# Sensor_Acquisition_Board_Rev2.net
KiCad netlist of a schematic drawn in EAGLE
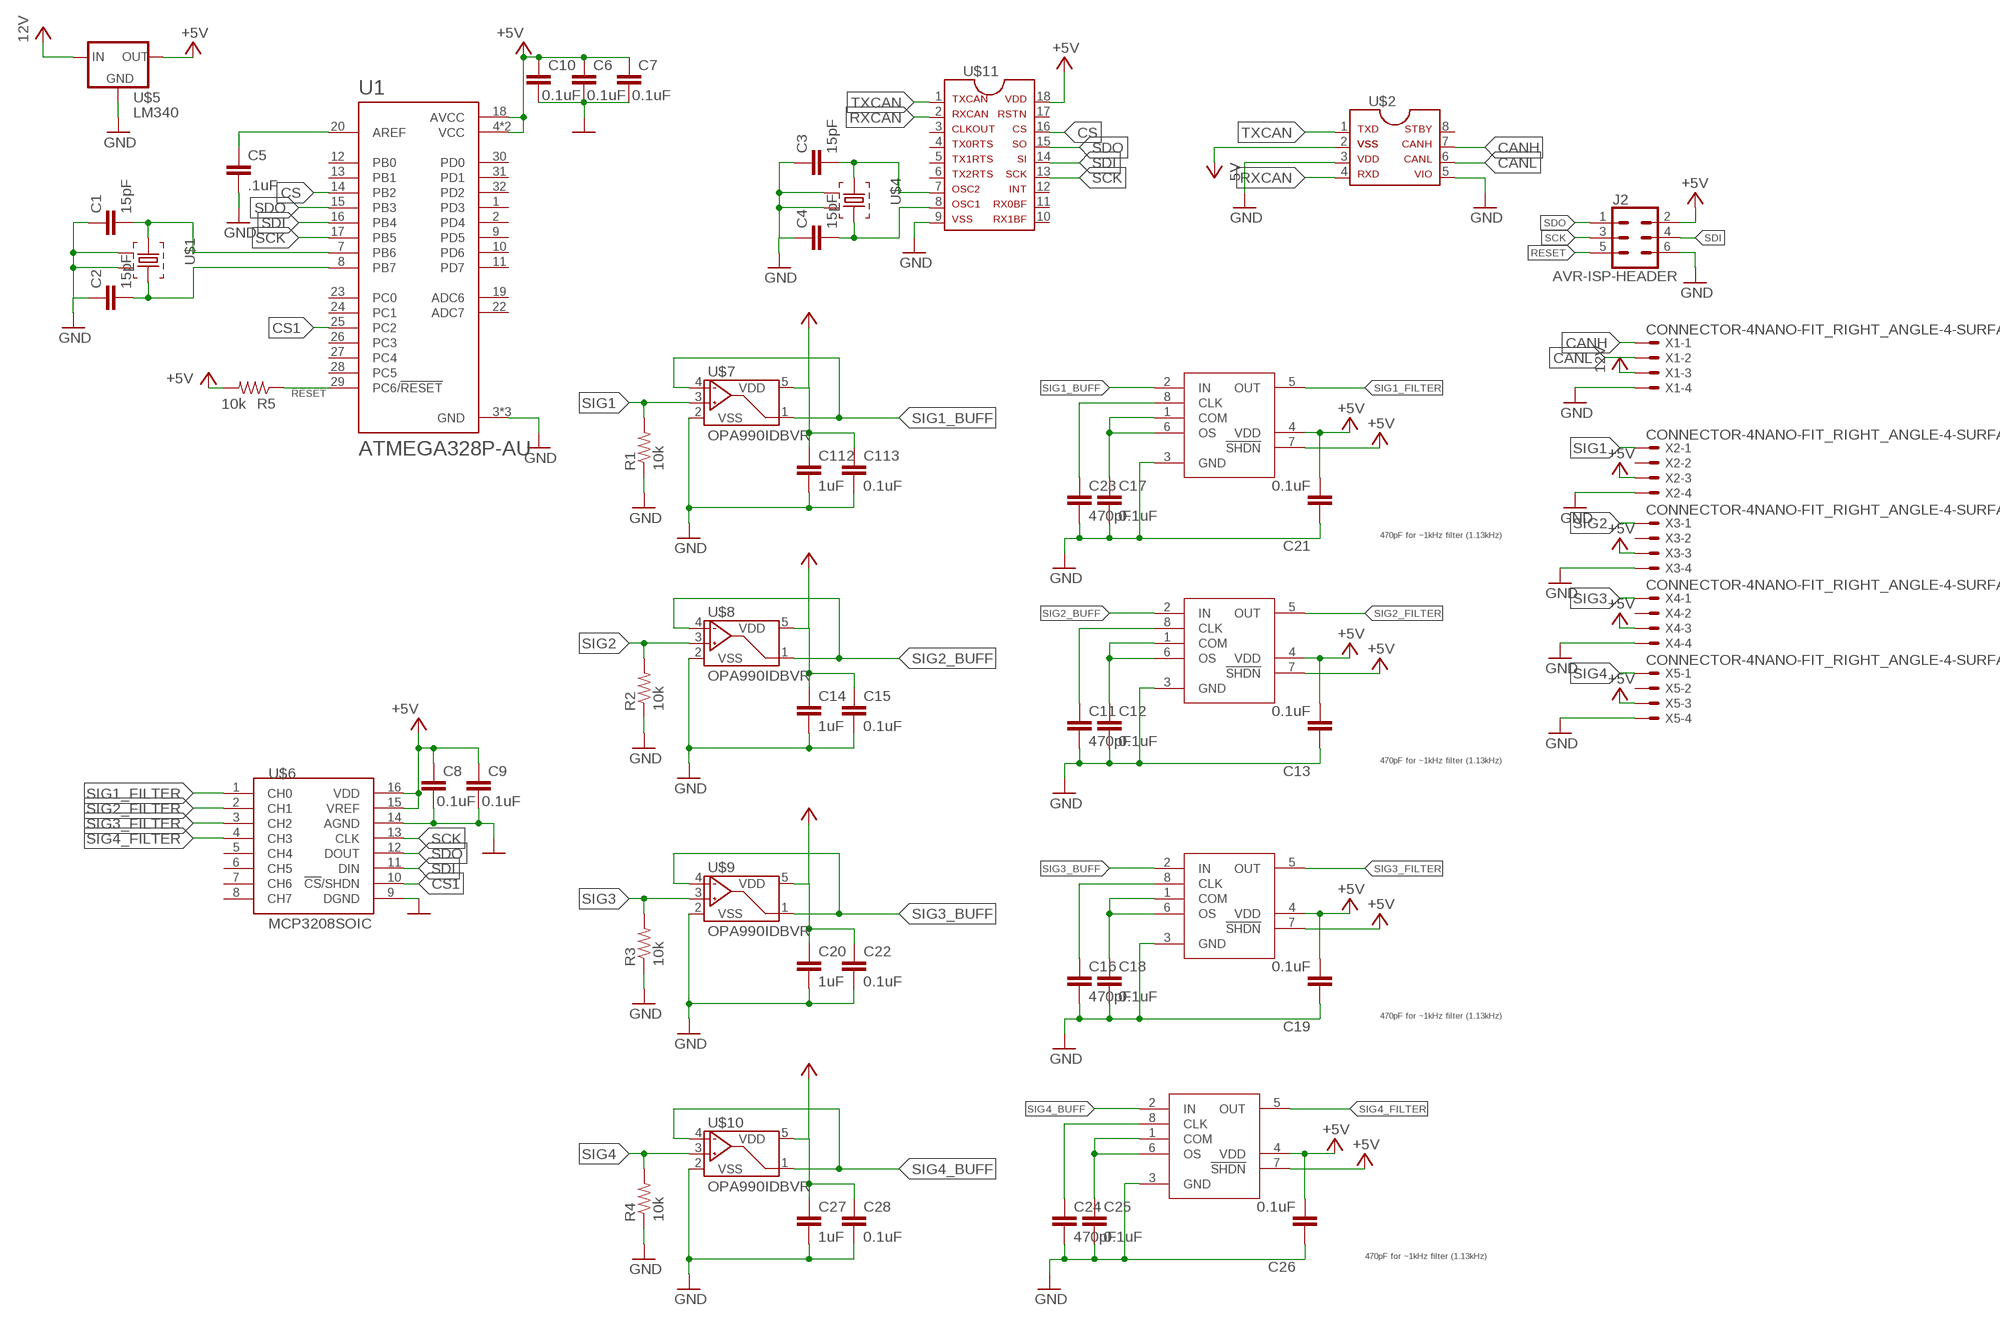
[diagram p0: schematic, sheet 1]

(export (version "E")
  (design (tool "Eeschema 10.0.6"))
  (components
    (comp (ref "C1")
      (value "15pF")
      (footprint "eagle-import:0603-CAP")
      (libsource (lib "eagle-import") (part "CAP0603-CAP"))
    )
    (comp (ref "C2")
      (value "15pF")
      (footprint "eagle-import:0603-CAP")
      (libsource (lib "eagle-import") (part "CAP0603-CAP"))
    )
    (comp (ref "C3")
      (value "15pF")
      (footprint "eagle-import:0603-CAP")
      (libsource (lib "eagle-import") (part "CAP0603-CAP"))
    )
    (comp (ref "C4")
      (value "15pF")
      (footprint "eagle-import:0603-CAP")
      (libsource (lib "eagle-import") (part "CAP0603-CAP"))
    )
    (comp (ref "C5")
      (value ".1uF")
      (footprint "eagle-import:0603-CAP")
      (libsource (lib "eagle-import") (part "CAP0603-CAP"))
    )
    (comp (ref "C6")
      (value "0.1uF")
      (footprint "eagle-import:0603-CAP")
      (libsource (lib "eagle-import") (part "CAP0603-CAP"))
    )
    (comp (ref "C7")
      (value "0.1uF")
      (footprint "eagle-import:0603-CAP")
      (libsource (lib "eagle-import") (part "CAP0603-CAP"))
    )
    (comp (ref "C8")
      (value "0.1uF")
      (footprint "eagle-import:0603-CAP")
      (libsource (lib "eagle-import") (part "CAP0603-CAP"))
    )
    (comp (ref "C9")
      (value "0.1uF")
      (footprint "eagle-import:0603-CAP")
      (libsource (lib "eagle-import") (part "CAP0603-CAP"))
    )
    (comp (ref "C10")
      (value "0.1uF")
      (footprint "eagle-import:0603-CAP")
      (libsource (lib "eagle-import") (part "CAP0603-CAP"))
    )
    (comp (ref "C11")
      (value "470pF")
      (footprint "eagle-import:0603-CAP")
      (libsource (lib "eagle-import") (part "CAP0603-CAP"))
    )
    (comp (ref "C12")
      (value "0.1uF")
      (footprint "eagle-import:0603-CAP")
      (libsource (lib "eagle-import") (part "CAP0603-CAP"))
    )
    (comp (ref "C13")
      (value "0.1uF")
      (footprint "eagle-import:0603-CAP")
      (libsource (lib "eagle-import") (part "CAP0603-CAP"))
    )
    (comp (ref "C14")
      (value "1uF")
      (footprint "eagle-import:0603-CAP")
      (libsource (lib "eagle-import") (part "CAP0603-CAP"))
    )
    (comp (ref "C15")
      (value "0.1uF")
      (footprint "eagle-import:0603-CAP")
      (libsource (lib "eagle-import") (part "CAP0603-CAP"))
    )
    (comp (ref "C16")
      (value "470pF")
      (footprint "eagle-import:0603-CAP")
      (libsource (lib "eagle-import") (part "CAP0603-CAP"))
    )
    (comp (ref "C17")
      (value "0.1uF")
      (footprint "eagle-import:0603-CAP")
      (libsource (lib "eagle-import") (part "CAP0603-CAP"))
    )
    (comp (ref "C18")
      (value "0.1uF")
      (footprint "eagle-import:0603-CAP")
      (libsource (lib "eagle-import") (part "CAP0603-CAP"))
    )
    (comp (ref "C19")
      (value "0.1uF")
      (footprint "eagle-import:0603-CAP")
      (libsource (lib "eagle-import") (part "CAP0603-CAP"))
    )
    (comp (ref "C20")
      (value "1uF")
      (footprint "eagle-import:0603-CAP")
      (libsource (lib "eagle-import") (part "CAP0603-CAP"))
    )
    (comp (ref "C21")
      (value "0.1uF")
      (footprint "eagle-import:0603-CAP")
      (libsource (lib "eagle-import") (part "CAP0603-CAP"))
    )
    (comp (ref "C22")
      (value "0.1uF")
      (footprint "eagle-import:0603-CAP")
      (libsource (lib "eagle-import") (part "CAP0603-CAP"))
    )
    (comp (ref "C23")
      (value "470pF")
      (footprint "eagle-import:0603-CAP")
      (libsource (lib "eagle-import") (part "CAP0603-CAP"))
    )
    (comp (ref "C24")
      (value "470pF")
      (footprint "eagle-import:0603-CAP")
      (libsource (lib "eagle-import") (part "CAP0603-CAP"))
    )
    (comp (ref "C25")
      (value "0.1uF")
      (footprint "eagle-import:0603-CAP")
      (libsource (lib "eagle-import") (part "CAP0603-CAP"))
    )
    (comp (ref "C26")
      (value "0.1uF")
      (footprint "eagle-import:0603-CAP")
      (libsource (lib "eagle-import") (part "CAP0603-CAP"))
    )
    (comp (ref "C27")
      (value "1uF")
      (footprint "eagle-import:0603-CAP")
      (libsource (lib "eagle-import") (part "CAP0603-CAP"))
    )
    (comp (ref "C28")
      (value "0.1uF")
      (footprint "eagle-import:0603-CAP")
      (libsource (lib "eagle-import") (part "CAP0603-CAP"))
    )
    (comp (ref "C112")
      (value "1uF")
      (footprint "eagle-import:0603-CAP")
      (libsource (lib "eagle-import") (part "CAP0603-CAP"))
    )
    (comp (ref "C113")
      (value "0.1uF")
      (footprint "eagle-import:0603-CAP")
      (libsource (lib "eagle-import") (part "CAP0603-CAP"))
    )
    (comp (ref "J2")
      (value "AVR-ISP-HEADER")
      (footprint "eagle-import:2X03@1")
      (libsource (lib "eagle-import") (part "AVR-ISP-HEADER"))
    )
    (comp (ref "R1")
      (value "10k")
      (footprint "eagle-import:0603-RES")
      (libsource (lib "eagle-import") (part "RESISTOR0603"))
    )
    (comp (ref "R2")
      (value "10k")
      (footprint "eagle-import:0603-RES")
      (libsource (lib "eagle-import") (part "RESISTOR0603"))
    )
    (comp (ref "R3")
      (value "10k")
      (footprint "eagle-import:0603-RES")
      (libsource (lib "eagle-import") (part "RESISTOR0603"))
    )
    (comp (ref "R4")
      (value "10k")
      (footprint "eagle-import:0603-RES")
      (libsource (lib "eagle-import") (part "RESISTOR0603"))
    )
    (comp (ref "R5")
      (value "10k")
      (footprint "eagle-import:0603-RES")
      (libsource (lib "eagle-import") (part "RESISTOR0603"))
    )
    (comp (ref "U$1")
      (value "ABM3B")
      (footprint "eagle-import:ABM3B")
      (libsource (lib "eagle-import") (part "ABM3B"))
    )
    (comp (ref "U$2")
      (value "MCP2562FDSOIC-08")
      (footprint "eagle-import:SOIC-08")
      (libsource (lib "eagle-import") (part "MCP2562FDSOIC-08"))
    )
    (comp (ref "U$4")
      (value "ABM3B")
      (footprint "eagle-import:ABM3B")
      (libsource (lib "eagle-import") (part "ABM3B"))
    )
    (comp (ref "U$5")
      (value "LM340")
      (footprint "eagle-import:SOT223")
      (libsource (lib "eagle-import") (part "LM340"))
    )
    (comp (ref "U$6")
      (value "MCP3208SOIC")
      (footprint "eagle-import:SOIC-16")
      (libsource (lib "eagle-import") (part "MCP3208SOIC"))
    )
    (comp (ref "U$7")
      (value "OPA990IDBVR")
      (footprint "eagle-import:SOT-23-5")
      (libsource (lib "eagle-import") (part "OPA990IDBVR"))
    )
    (comp (ref "U$8")
      (value "OPA990IDBVR")
      (footprint "eagle-import:SOT-23-5")
      (libsource (lib "eagle-import") (part "OPA990IDBVR"))
    )
    (comp (ref "U$9")
      (value "OPA990IDBVR")
      (footprint "eagle-import:SOT-23-5")
      (libsource (lib "eagle-import") (part "OPA990IDBVR"))
    )
    (comp (ref "U$10")
      (value "OPA990IDBVR")
      (footprint "eagle-import:SOT-23-5")
      (libsource (lib "eagle-import") (part "OPA990IDBVR"))
    )
    (comp (ref "U$11")
      (value "MCP2515SMD")
      (footprint "eagle-import:SOIC-18W")
      (libsource (lib "eagle-import") (part "MCP2515SMD"))
    )
    (comp (ref "U1")
      (value "ATMEGA328P-AU")
      (footprint "eagle-import:QFP80P900X900X120-32N")
      (fields (field (name "MF") "Microchip"))
      (libsource (lib "eagle-import") (part "ATMEGA328P-AU"))
    )
    (comp (ref "U2")
      (value "MAX7480")
      (footprint "eagle-import:SOP8")
      (libsource (lib "eagle-import") (part "MAX7400"))
    )
    (comp (ref "U3")
      (value "MAX7480")
      (footprint "eagle-import:SOP8")
      (libsource (lib "eagle-import") (part "MAX7400"))
    )
    (comp (ref "U4")
      (value "MAX7480")
      (footprint "eagle-import:SOP8")
      (libsource (lib "eagle-import") (part "MAX7400"))
    )
    (comp (ref "U24")
      (value "MAX7480")
      (footprint "eagle-import:SOP8")
      (libsource (lib "eagle-import") (part "MAX7400"))
    )
    (comp (ref "X1")
      (value "CONNECTOR-4NANO-FIT_RIGHT_ANGLE-4-SURFACE")
      (footprint "eagle-import:NANO-FIT_RIGHT_ANGLE-4-SURFACE")
      (libsource (lib "eagle-import") (part "CONNECTOR-4NANO-FIT_RIGHT_ANGLE-4-SURFACE"))
    )
    (comp (ref "X2")
      (value "CONNECTOR-4NANO-FIT_RIGHT_ANGLE-4-SURFACE")
      (footprint "eagle-import:NANO-FIT_RIGHT_ANGLE-4-SURFACE")
      (libsource (lib "eagle-import") (part "CONNECTOR-4NANO-FIT_RIGHT_ANGLE-4-SURFACE"))
    )
    (comp (ref "X3")
      (value "CONNECTOR-4NANO-FIT_RIGHT_ANGLE-4-SURFACE")
      (footprint "eagle-import:NANO-FIT_RIGHT_ANGLE-4-SURFACE")
      (libsource (lib "eagle-import") (part "CONNECTOR-4NANO-FIT_RIGHT_ANGLE-4-SURFACE"))
    )
    (comp (ref "X4")
      (value "CONNECTOR-4NANO-FIT_RIGHT_ANGLE-4-SURFACE")
      (footprint "eagle-import:NANO-FIT_RIGHT_ANGLE-4-SURFACE")
      (libsource (lib "eagle-import") (part "CONNECTOR-4NANO-FIT_RIGHT_ANGLE-4-SURFACE"))
    )
    (comp (ref "X5")
      (value "CONNECTOR-4NANO-FIT_RIGHT_ANGLE-4-SURFACE")
      (footprint "eagle-import:NANO-FIT_RIGHT_ANGLE-4-SURFACE")
      (libsource (lib "eagle-import") (part "CONNECTOR-4NANO-FIT_RIGHT_ANGLE-4-SURFACE"))
    )
  )
  (nets
    (net (code "1") (name "+5V") (class "Default")
      (node (ref "C10") (pin "1") (pinfunction "1_1") (pintype "passive"))
      (node (ref "C112") (pin "1") (pinfunction "1_1") (pintype "passive"))
      (node (ref "C113") (pin "1") (pinfunction "1_1") (pintype "passive"))
      (node (ref "C13") (pin "2") (pinfunction "2_2") (pintype "passive"))
      (node (ref "C14") (pin "1") (pinfunction "1_1") (pintype "passive"))
      (node (ref "C15") (pin "1") (pinfunction "1_1") (pintype "passive"))
      (node (ref "C19") (pin "2") (pinfunction "2_2") (pintype "passive"))
      (node (ref "C20") (pin "1") (pinfunction "1_1") (pintype "passive"))
      (node (ref "C21") (pin "2") (pinfunction "2_2") (pintype "passive"))
      (node (ref "C22") (pin "1") (pinfunction "1_1") (pintype "passive"))
      (node (ref "C26") (pin "2") (pinfunction "2_2") (pintype "passive"))
      (node (ref "C27") (pin "1") (pinfunction "1_1") (pintype "passive"))
      (node (ref "C28") (pin "1") (pinfunction "1_1") (pintype "passive"))
      (node (ref "C6") (pin "1") (pinfunction "1_1") (pintype "passive"))
      (node (ref "C7") (pin "1") (pinfunction "1_1") (pintype "passive"))
      (node (ref "C8") (pin "1") (pinfunction "1_1") (pintype "passive"))
      (node (ref "C9") (pin "1") (pinfunction "1_1") (pintype "passive"))
      (node (ref "J2") (pin "2") (pinfunction "2_2") (pintype "passive"))
      (node (ref "R5") (pin "2") (pinfunction "2_2") (pintype "passive"))
      (node (ref "U$10") (pin "5") (pinfunction "VDD_5") (pintype "passive"))
      (node (ref "U$11") (pin "18") (pinfunction "VDD_18") (pintype "passive"))
      (node (ref "U$5") (pin "3") (pinfunction "OUT_3") (pintype "output"))
      (node (ref "U$6") (pin "15") (pinfunction "VREF_15") (pintype "bidirectional"))
      (node (ref "U$6") (pin "16") (pinfunction "VDD_16") (pintype "bidirectional"))
      (node (ref "U$7") (pin "5") (pinfunction "VDD_5") (pintype "passive"))
      (node (ref "U$8") (pin "5") (pinfunction "VDD_5") (pintype "passive"))
      (node (ref "U$9") (pin "5") (pinfunction "VDD_5") (pintype "passive"))
      (node (ref "U1") (pin "18") (pinfunction "AVCC_18") (pintype "power_in"))
      (node (ref "U1") (pin "4") (pinfunction "VCC_4") (pintype "power_in"))
      (node (ref "U1") (pin "6") (pinfunction "VCC_6") (pintype "power_in"))
      (node (ref "U2") (pin "4") (pinfunction "VDD_4") (pintype "bidirectional"))
      (node (ref "U2") (pin "7") (pinfunction "~{SHDN}_7") (pintype "bidirectional"))
      (node (ref "U24") (pin "4") (pinfunction "VDD_4") (pintype "bidirectional"))
      (node (ref "U24") (pin "7") (pinfunction "~{SHDN}_7") (pintype "bidirectional"))
      (node (ref "U3") (pin "4") (pinfunction "VDD_4") (pintype "bidirectional"))
      (node (ref "U3") (pin "7") (pinfunction "~{SHDN}_7") (pintype "bidirectional"))
      (node (ref "U4") (pin "4") (pinfunction "VDD_4") (pintype "bidirectional"))
      (node (ref "U4") (pin "7") (pinfunction "~{SHDN}_7") (pintype "bidirectional"))
      (node (ref "X2") (pin "3") (pinfunction "S_3") (pintype "passive"))
      (node (ref "X3") (pin "3") (pinfunction "S_3") (pintype "passive"))
      (node (ref "X4") (pin "3") (pinfunction "S_3") (pintype "passive"))
      (node (ref "X5") (pin "3") (pinfunction "S_3") (pintype "passive"))
    )
    (net (code "2") (name "12V") (class "Default")
      (node (ref "U$2") (pin "2") (pinfunction "2_2") (pintype "passive"))
      (node (ref "U$5") (pin "1") (pinfunction "IN_1") (pintype "input"))
      (node (ref "X1") (pin "3") (pinfunction "S_3") (pintype "passive"))
    )
    (net (code "3") (name "CANH") (class "Default")
      (node (ref "U$2") (pin "7") (pinfunction "7_7") (pintype "passive"))
      (node (ref "X1") (pin "1") (pinfunction "S_1") (pintype "passive"))
    )
    (net (code "4") (name "CANL") (class "Default")
      (node (ref "U$2") (pin "6") (pinfunction "6_6") (pintype "passive"))
      (node (ref "X1") (pin "2") (pinfunction "S_2") (pintype "passive"))
    )
    (net (code "5") (name "CS") (class "Default")
      (node (ref "U$11") (pin "16") (pinfunction "CS_16") (pintype "passive"))
      (node (ref "U1") (pin "14") (pinfunction "PB2_14") (pintype "bidirectional"))
    )
    (net (code "6") (name "CS1") (class "Default")
      (node (ref "U$6") (pin "10") (pinfunction "~{CS}/SHDN_10") (pintype "bidirectional"))
      (node (ref "U1") (pin "25") (pinfunction "PC2_25") (pintype "bidirectional"))
    )
    (net (code "7") (name "GND") (class "Default")
      (node (ref "C1") (pin "1") (pinfunction "1_1") (pintype "passive"))
      (node (ref "C10") (pin "2") (pinfunction "2_2") (pintype "passive"))
      (node (ref "C11") (pin "2") (pinfunction "2_2") (pintype "passive"))
      (node (ref "C112") (pin "2") (pinfunction "2_2") (pintype "passive"))
      (node (ref "C113") (pin "2") (pinfunction "2_2") (pintype "passive"))
      (node (ref "C12") (pin "2") (pinfunction "2_2") (pintype "passive"))
      (node (ref "C13") (pin "1") (pinfunction "1_1") (pintype "passive"))
      (node (ref "C14") (pin "2") (pinfunction "2_2") (pintype "passive"))
      (node (ref "C15") (pin "2") (pinfunction "2_2") (pintype "passive"))
      (node (ref "C16") (pin "2") (pinfunction "2_2") (pintype "passive"))
      (node (ref "C17") (pin "2") (pinfunction "2_2") (pintype "passive"))
      (node (ref "C18") (pin "2") (pinfunction "2_2") (pintype "passive"))
      (node (ref "C19") (pin "1") (pinfunction "1_1") (pintype "passive"))
      (node (ref "C2") (pin "1") (pinfunction "1_1") (pintype "passive"))
      (node (ref "C20") (pin "2") (pinfunction "2_2") (pintype "passive"))
      (node (ref "C21") (pin "1") (pinfunction "1_1") (pintype "passive"))
      (node (ref "C22") (pin "2") (pinfunction "2_2") (pintype "passive"))
      (node (ref "C23") (pin "2") (pinfunction "2_2") (pintype "passive"))
      (node (ref "C24") (pin "2") (pinfunction "2_2") (pintype "passive"))
      (node (ref "C25") (pin "2") (pinfunction "2_2") (pintype "passive"))
      (node (ref "C26") (pin "1") (pinfunction "1_1") (pintype "passive"))
      (node (ref "C27") (pin "2") (pinfunction "2_2") (pintype "passive"))
      (node (ref "C28") (pin "2") (pinfunction "2_2") (pintype "passive"))
      (node (ref "C3") (pin "1") (pinfunction "1_1") (pintype "passive"))
      (node (ref "C4") (pin "1") (pinfunction "1_1") (pintype "passive"))
      (node (ref "C5") (pin "2") (pinfunction "2_2") (pintype "passive"))
      (node (ref "C6") (pin "2") (pinfunction "2_2") (pintype "passive"))
      (node (ref "C7") (pin "2") (pinfunction "2_2") (pintype "passive"))
      (node (ref "C8") (pin "2") (pinfunction "2_2") (pintype "passive"))
      (node (ref "C9") (pin "2") (pinfunction "2_2") (pintype "passive"))
      (node (ref "J2") (pin "6") (pinfunction "6_6") (pintype "passive"))
      (node (ref "R1") (pin "1") (pinfunction "1_1") (pintype "passive"))
      (node (ref "R2") (pin "1") (pinfunction "1_1") (pintype "passive"))
      (node (ref "R3") (pin "1") (pinfunction "1_1") (pintype "passive"))
      (node (ref "R4") (pin "1") (pinfunction "1_1") (pintype "passive"))
      (node (ref "U$1") (pin "GND") (pinfunction "GND_GND") (pintype "passive"))
      (node (ref "U$1") (pin "GND2") (pinfunction "GND2_GND2") (pintype "passive"))
      (node (ref "U$10") (pin "2") (pinfunction "VSS_2") (pintype "passive"))
      (node (ref "U$11") (pin "9") (pinfunction "VSS_9") (pintype "passive"))
      (node (ref "U$2") (pin "3") (pinfunction "3_3") (pintype "passive"))
      (node (ref "U$2") (pin "5") (pinfunction "5_5") (pintype "passive"))
      (node (ref "U$4") (pin "GND") (pinfunction "GND_GND") (pintype "passive"))
      (node (ref "U$4") (pin "GND2") (pinfunction "GND2_GND2") (pintype "passive"))
      (node (ref "U$5") (pin "2") (pinfunction "GND_2") (pintype "input"))
      (node (ref "U$5") (pin "4") (pinfunction "GND_4") (pintype "input"))
      (node (ref "U$6") (pin "14") (pinfunction "AGND_14") (pintype "bidirectional"))
      (node (ref "U$6") (pin "9") (pinfunction "DGND_9") (pintype "bidirectional"))
      (node (ref "U$7") (pin "2") (pinfunction "VSS_2") (pintype "passive"))
      (node (ref "U$8") (pin "2") (pinfunction "VSS_2") (pintype "passive"))
      (node (ref "U$9") (pin "2") (pinfunction "VSS_2") (pintype "passive"))
      (node (ref "U1") (pin "21") (pinfunction "GND_21") (pintype "power_in"))
      (node (ref "U1") (pin "3") (pinfunction "GND_3") (pintype "power_in"))
      (node (ref "U1") (pin "5") (pinfunction "GND_5") (pintype "power_in"))
      (node (ref "U2") (pin "3") (pinfunction "GND_3") (pintype "bidirectional"))
      (node (ref "U24") (pin "3") (pinfunction "GND_3") (pintype "bidirectional"))
      (node (ref "U3") (pin "3") (pinfunction "GND_3") (pintype "bidirectional"))
      (node (ref "U4") (pin "3") (pinfunction "GND_3") (pintype "bidirectional"))
      (node (ref "X1") (pin "4") (pinfunction "S_4") (pintype "passive"))
      (node (ref "X2") (pin "4") (pinfunction "S_4") (pintype "passive"))
      (node (ref "X3") (pin "4") (pinfunction "S_4") (pintype "passive"))
      (node (ref "X4") (pin "4") (pinfunction "S_4") (pintype "passive"))
      (node (ref "X5") (pin "4") (pinfunction "S_4") (pintype "passive"))
    )
    (net (code "8") (name "Net-(U$11-OSC1)") (class "Default")
      (node (ref "C4") (pin "2") (pinfunction "2_2") (pintype "passive"))
      (node (ref "U$11") (pin "8") (pinfunction "OSC1_8") (pintype "passive"))
      (node (ref "U$4") (pin "3") (pinfunction "3_3") (pintype "passive"))
    )
    (net (code "9") (name "Net-(U$11-OSC2)") (class "Default")
      (node (ref "C3") (pin "2") (pinfunction "2_2") (pintype "passive"))
      (node (ref "U$11") (pin "7") (pinfunction "OSC2_7") (pintype "passive"))
      (node (ref "U$4") (pin "1") (pinfunction "1_1") (pintype "passive"))
    )
    (net (code "10") (name "Net-(U1-AREF)") (class "Default")
      (node (ref "C5") (pin "1") (pinfunction "1_1") (pintype "passive"))
      (node (ref "U1") (pin "20") (pinfunction "AREF_20") (pintype "input"))
    )
    (net (code "11") (name "Net-(U1-PB6)") (class "Default")
      (node (ref "C1") (pin "2") (pinfunction "2_2") (pintype "passive"))
      (node (ref "U$1") (pin "1") (pinfunction "1_1") (pintype "passive"))
      (node (ref "U1") (pin "7") (pinfunction "PB6_7") (pintype "bidirectional"))
    )
    (net (code "12") (name "Net-(U1-PB7)") (class "Default")
      (node (ref "C2") (pin "2") (pinfunction "2_2") (pintype "passive"))
      (node (ref "U$1") (pin "3") (pinfunction "3_3") (pintype "passive"))
      (node (ref "U1") (pin "8") (pinfunction "PB7_8") (pintype "bidirectional"))
    )
    (net (code "13") (name "Net-(U2-CLK)") (class "Default")
      (node (ref "C11") (pin "1") (pinfunction "1_1") (pintype "passive"))
      (node (ref "U2") (pin "8") (pinfunction "CLK_8") (pintype "bidirectional"))
    )
    (net (code "14") (name "Net-(U2-COM)") (class "Default")
      (node (ref "C12") (pin "1") (pinfunction "1_1") (pintype "passive"))
      (node (ref "U2") (pin "1") (pinfunction "COM_1") (pintype "bidirectional"))
      (node (ref "U2") (pin "6") (pinfunction "OS_6") (pintype "bidirectional"))
    )
    (net (code "15") (name "Net-(U3-CLK)") (class "Default")
      (node (ref "C16") (pin "1") (pinfunction "1_1") (pintype "passive"))
      (node (ref "U3") (pin "8") (pinfunction "CLK_8") (pintype "bidirectional"))
    )
    (net (code "16") (name "Net-(U3-COM)") (class "Default")
      (node (ref "C18") (pin "1") (pinfunction "1_1") (pintype "passive"))
      (node (ref "U3") (pin "1") (pinfunction "COM_1") (pintype "bidirectional"))
      (node (ref "U3") (pin "6") (pinfunction "OS_6") (pintype "bidirectional"))
    )
    (net (code "17") (name "Net-(U4-CLK)") (class "Default")
      (node (ref "C24") (pin "1") (pinfunction "1_1") (pintype "passive"))
      (node (ref "U4") (pin "8") (pinfunction "CLK_8") (pintype "bidirectional"))
    )
    (net (code "18") (name "Net-(U4-COM)") (class "Default")
      (node (ref "C25") (pin "1") (pinfunction "1_1") (pintype "passive"))
      (node (ref "U4") (pin "1") (pinfunction "COM_1") (pintype "bidirectional"))
      (node (ref "U4") (pin "6") (pinfunction "OS_6") (pintype "bidirectional"))
    )
    (net (code "19") (name "Net-(U24-CLK)") (class "Default")
      (node (ref "C23") (pin "1") (pinfunction "1_1") (pintype "passive"))
      (node (ref "U24") (pin "8") (pinfunction "CLK_8") (pintype "bidirectional"))
    )
    (net (code "20") (name "Net-(U24-COM)") (class "Default")
      (node (ref "C17") (pin "1") (pinfunction "1_1") (pintype "passive"))
      (node (ref "U24") (pin "1") (pinfunction "COM_1") (pintype "bidirectional"))
      (node (ref "U24") (pin "6") (pinfunction "OS_6") (pintype "bidirectional"))
    )
    (net (code "21") (name "RESET") (class "Default")
      (node (ref "J2") (pin "5") (pinfunction "5_5") (pintype "passive"))
      (node (ref "R5") (pin "1") (pinfunction "1_1") (pintype "passive"))
      (node (ref "U1") (pin "29") (pinfunction "PC6/~{RESET}_29") (pintype "bidirectional"))
    )
    (net (code "22") (name "RXCAN") (class "Default")
      (node (ref "U$11") (pin "2") (pinfunction "RXCAN_2") (pintype "passive"))
      (node (ref "U$2") (pin "4") (pinfunction "4_4") (pintype "passive"))
    )
    (net (code "23") (name "SCK") (class "Default")
      (node (ref "J2") (pin "3") (pinfunction "3_3") (pintype "passive"))
      (node (ref "U$11") (pin "13") (pinfunction "SCK_13") (pintype "passive"))
      (node (ref "U$6") (pin "13") (pinfunction "CLK_13") (pintype "bidirectional"))
      (node (ref "U1") (pin "17") (pinfunction "PB5_17") (pintype "bidirectional"))
    )
    (net (code "24") (name "SDI") (class "Default")
      (node (ref "J2") (pin "4") (pinfunction "4_4") (pintype "passive"))
      (node (ref "U$11") (pin "14") (pinfunction "SI_14") (pintype "passive"))
      (node (ref "U$6") (pin "11") (pinfunction "DIN_11") (pintype "bidirectional"))
      (node (ref "U1") (pin "16") (pinfunction "PB4_16") (pintype "bidirectional"))
    )
    (net (code "25") (name "SDO") (class "Default")
      (node (ref "J2") (pin "1") (pinfunction "1_1") (pintype "passive"))
      (node (ref "U$11") (pin "15") (pinfunction "SO_15") (pintype "passive"))
      (node (ref "U$6") (pin "12") (pinfunction "DOUT_12") (pintype "bidirectional"))
      (node (ref "U1") (pin "15") (pinfunction "PB3_15") (pintype "bidirectional"))
    )
    (net (code "26") (name "SIG1") (class "Default")
      (node (ref "R1") (pin "2") (pinfunction "2_2") (pintype "passive"))
      (node (ref "U$7") (pin "3") (pinfunction "VIN+_3") (pintype "passive"))
      (node (ref "X2") (pin "1") (pinfunction "S_1") (pintype "passive"))
    )
    (net (code "27") (name "SIG1_BUFF") (class "Default")
      (node (ref "U$7") (pin "1") (pinfunction "VOUT_1") (pintype "passive"))
      (node (ref "U$7") (pin "4") (pinfunction "VIN-_4") (pintype "passive"))
      (node (ref "U24") (pin "2") (pinfunction "IN_2") (pintype "bidirectional"))
    )
    (net (code "28") (name "SIG1_FILTER") (class "Default")
      (node (ref "U$6") (pin "1") (pinfunction "CH0_1") (pintype "bidirectional"))
      (node (ref "U24") (pin "5") (pinfunction "OUT_5") (pintype "bidirectional"))
    )
    (net (code "29") (name "SIG2") (class "Default")
      (node (ref "R2") (pin "2") (pinfunction "2_2") (pintype "passive"))
      (node (ref "U$8") (pin "3") (pinfunction "VIN+_3") (pintype "passive"))
      (node (ref "X3") (pin "1") (pinfunction "S_1") (pintype "passive"))
    )
    (net (code "30") (name "SIG2_BUFF") (class "Default")
      (node (ref "U$8") (pin "1") (pinfunction "VOUT_1") (pintype "passive"))
      (node (ref "U$8") (pin "4") (pinfunction "VIN-_4") (pintype "passive"))
      (node (ref "U2") (pin "2") (pinfunction "IN_2") (pintype "bidirectional"))
    )
    (net (code "31") (name "SIG2_FILTER") (class "Default")
      (node (ref "U$6") (pin "2") (pinfunction "CH1_2") (pintype "bidirectional"))
      (node (ref "U2") (pin "5") (pinfunction "OUT_5") (pintype "bidirectional"))
    )
    (net (code "32") (name "SIG3") (class "Default")
      (node (ref "R3") (pin "2") (pinfunction "2_2") (pintype "passive"))
      (node (ref "U$9") (pin "3") (pinfunction "VIN+_3") (pintype "passive"))
      (node (ref "X4") (pin "1") (pinfunction "S_1") (pintype "passive"))
    )
    (net (code "33") (name "SIG3_BUFF") (class "Default")
      (node (ref "U$9") (pin "1") (pinfunction "VOUT_1") (pintype "passive"))
      (node (ref "U$9") (pin "4") (pinfunction "VIN-_4") (pintype "passive"))
      (node (ref "U3") (pin "2") (pinfunction "IN_2") (pintype "bidirectional"))
    )
    (net (code "34") (name "SIG3_FILTER") (class "Default")
      (node (ref "U$6") (pin "3") (pinfunction "CH2_3") (pintype "bidirectional"))
      (node (ref "U3") (pin "5") (pinfunction "OUT_5") (pintype "bidirectional"))
    )
    (net (code "35") (name "SIG4") (class "Default")
      (node (ref "R4") (pin "2") (pinfunction "2_2") (pintype "passive"))
      (node (ref "U$10") (pin "3") (pinfunction "VIN+_3") (pintype "passive"))
      (node (ref "X5") (pin "1") (pinfunction "S_1") (pintype "passive"))
    )
    (net (code "36") (name "SIG4_BUFF") (class "Default")
      (node (ref "U$10") (pin "1") (pinfunction "VOUT_1") (pintype "passive"))
      (node (ref "U$10") (pin "4") (pinfunction "VIN-_4") (pintype "passive"))
      (node (ref "U4") (pin "2") (pinfunction "IN_2") (pintype "bidirectional"))
    )
    (net (code "37") (name "SIG4_FILTER") (class "Default")
      (node (ref "U$6") (pin "4") (pinfunction "CH3_4") (pintype "bidirectional"))
      (node (ref "U4") (pin "5") (pinfunction "OUT_5") (pintype "bidirectional"))
    )
    (net (code "38") (name "TXCAN") (class "Default")
      (node (ref "U$11") (pin "1") (pinfunction "TXCAN_1") (pintype "passive"))
      (node (ref "U$2") (pin "1") (pinfunction "1_1") (pintype "passive"))
    )
    (net (code "39") (name "unconnected-(U$2-Pad8)") (class "Default")
      (node (ref "U$2") (pin "8") (pinfunction "8_8") (pintype "passive"))
    )
    (net (code "40") (name "unconnected-(U$6-CH4-Pad5)") (class "Default")
      (node (ref "U$6") (pin "5") (pinfunction "CH4_5") (pintype "bidirectional"))
    )
    (net (code "41") (name "unconnected-(U$6-CH5-Pad6)") (class "Default")
      (node (ref "U$6") (pin "6") (pinfunction "CH5_6") (pintype "bidirectional"))
    )
    (net (code "42") (name "unconnected-(U$6-CH6-Pad7)") (class "Default")
      (node (ref "U$6") (pin "7") (pinfunction "CH6_7") (pintype "bidirectional"))
    )
    (net (code "43") (name "unconnected-(U$6-CH7-Pad8)") (class "Default")
      (node (ref "U$6") (pin "8") (pinfunction "CH7_8") (pintype "bidirectional"))
    )
    (net (code "44") (name "unconnected-(U$11-CLKOUT-Pad3)") (class "Default")
      (node (ref "U$11") (pin "3") (pinfunction "CLKOUT_3") (pintype "passive"))
    )
    (net (code "45") (name "unconnected-(U$11-INT-Pad12)") (class "Default")
      (node (ref "U$11") (pin "12") (pinfunction "INT_12") (pintype "passive"))
    )
    (net (code "46") (name "unconnected-(U$11-RSTN-Pad17)") (class "Default")
      (node (ref "U$11") (pin "17") (pinfunction "RSTN_17") (pintype "passive"))
    )
    (net (code "47") (name "unconnected-(U$11-RX0BF-Pad11)") (class "Default")
      (node (ref "U$11") (pin "11") (pinfunction "RX0BF_11") (pintype "passive"))
    )
    (net (code "48") (name "unconnected-(U$11-RX1BF-Pad10)") (class "Default")
      (node (ref "U$11") (pin "10") (pinfunction "RX1BF_10") (pintype "passive"))
    )
    (net (code "49") (name "unconnected-(U$11-TX0RTS-Pad4)") (class "Default")
      (node (ref "U$11") (pin "4") (pinfunction "TX0RTS_4") (pintype "passive"))
    )
    (net (code "50") (name "unconnected-(U$11-TX1RTS-Pad5)") (class "Default")
      (node (ref "U$11") (pin "5") (pinfunction "TX1RTS_5") (pintype "passive"))
    )
    (net (code "51") (name "unconnected-(U$11-TX2RTS-Pad6)") (class "Default")
      (node (ref "U$11") (pin "6") (pinfunction "TX2RTS_6") (pintype "passive"))
    )
    (net (code "52") (name "unconnected-(U1-ADC6-Pad19)") (class "Default")
      (node (ref "U1") (pin "19") (pinfunction "ADC6_19") (pintype "bidirectional"))
    )
    (net (code "53") (name "unconnected-(U1-ADC7-Pad22)") (class "Default")
      (node (ref "U1") (pin "22") (pinfunction "ADC7_22") (pintype "bidirectional"))
    )
    (net (code "54") (name "unconnected-(U1-PB0-Pad12)") (class "Default")
      (node (ref "U1") (pin "12") (pinfunction "PB0_12") (pintype "bidirectional"))
    )
    (net (code "55") (name "unconnected-(U1-PB1-Pad13)") (class "Default")
      (node (ref "U1") (pin "13") (pinfunction "PB1_13") (pintype "bidirectional"))
    )
    (net (code "56") (name "unconnected-(U1-PC0-Pad23)") (class "Default")
      (node (ref "U1") (pin "23") (pinfunction "PC0_23") (pintype "bidirectional"))
    )
    (net (code "57") (name "unconnected-(U1-PC1-Pad24)") (class "Default")
      (node (ref "U1") (pin "24") (pinfunction "PC1_24") (pintype "bidirectional"))
    )
    (net (code "58") (name "unconnected-(U1-PC3-Pad26)") (class "Default")
      (node (ref "U1") (pin "26") (pinfunction "PC3_26") (pintype "bidirectional"))
    )
    (net (code "59") (name "unconnected-(U1-PC4-Pad27)") (class "Default")
      (node (ref "U1") (pin "27") (pinfunction "PC4_27") (pintype "bidirectional"))
    )
    (net (code "60") (name "unconnected-(U1-PC5-Pad28)") (class "Default")
      (node (ref "U1") (pin "28") (pinfunction "PC5_28") (pintype "bidirectional"))
    )
    (net (code "61") (name "unconnected-(U1-PD0-Pad30)") (class "Default")
      (node (ref "U1") (pin "30") (pinfunction "PD0_30") (pintype "bidirectional"))
    )
    (net (code "62") (name "unconnected-(U1-PD1-Pad31)") (class "Default")
      (node (ref "U1") (pin "31") (pinfunction "PD1_31") (pintype "bidirectional"))
    )
    (net (code "63") (name "unconnected-(U1-PD2-Pad32)") (class "Default")
      (node (ref "U1") (pin "32") (pinfunction "PD2_32") (pintype "bidirectional"))
    )
    (net (code "64") (name "unconnected-(U1-PD3-Pad1)") (class "Default")
      (node (ref "U1") (pin "1") (pinfunction "PD3_1") (pintype "bidirectional"))
    )
    (net (code "65") (name "unconnected-(U1-PD4-Pad2)") (class "Default")
      (node (ref "U1") (pin "2") (pinfunction "PD4_2") (pintype "bidirectional"))
    )
    (net (code "66") (name "unconnected-(U1-PD5-Pad9)") (class "Default")
      (node (ref "U1") (pin "9") (pinfunction "PD5_9") (pintype "bidirectional"))
    )
    (net (code "67") (name "unconnected-(U1-PD6-Pad10)") (class "Default")
      (node (ref "U1") (pin "10") (pinfunction "PD6_10") (pintype "bidirectional"))
    )
    (net (code "68") (name "unconnected-(U1-PD7-Pad11)") (class "Default")
      (node (ref "U1") (pin "11") (pinfunction "PD7_11") (pintype "bidirectional"))
    )
    (net (code "69") (name "unconnected-(X2B-S-Pad2)") (class "Default")
      (node (ref "X2") (pin "2") (pinfunction "S_2") (pintype "passive"))
    )
    (net (code "70") (name "unconnected-(X3B-S-Pad2)") (class "Default")
      (node (ref "X3") (pin "2") (pinfunction "S_2") (pintype "passive"))
    )
    (net (code "71") (name "unconnected-(X4B-S-Pad2)") (class "Default")
      (node (ref "X4") (pin "2") (pinfunction "S_2") (pintype "passive"))
    )
    (net (code "72") (name "unconnected-(X5B-S-Pad2)") (class "Default")
      (node (ref "X5") (pin "2") (pinfunction "S_2") (pintype "passive"))
    )
  )
)
